# 6_BATT_5V.net
KiCad netlist of a schematic drawn in Altium Designer
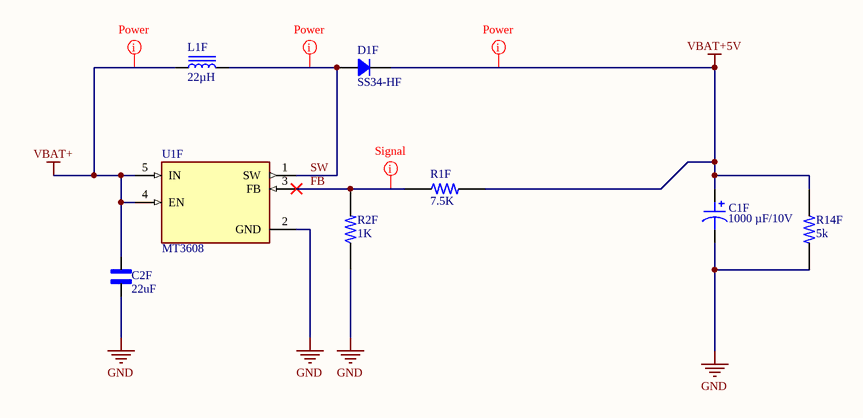
[diagram p0: 6_BATT+5V.SchDoc]

(export (version "E")
  (design (tool "Eeschema 10.0.6"))
  (components
    (comp (ref "C1F")
      (value "1000 µF/10V")
      (footprint "CAP AL TH D8 L3.5 H12.5")
      (description "CAP ALUM 1000UF 20% 6.3V RADIAL")
      (fields
        (field (name "PART NUMBER") "ECA-0JHG102")
        (field (name "MANUFACTURER") "Panasonic Electronic Components")
      )
      (libsource (lib "ESP-12F_WLED_IOT_LIPO") (part "Polarised Capacitor"))
    )
    (comp (ref "C2F")
      (value "22uF")
      (footprint "C-0603")
      (description "Ceramic Capacitor 16V 0603 (1608 Metric)")
      (fields (field (name "MP") "C0603C104J4RAC") (field (name "MF") "KEMET"))
      (libsource (lib "ESP-12F_WLED_IOT_LIPO") (part "C-0603"))
    )
    (comp (ref "D1F")
      (value "SS34-HF")
      (footprint "DO214AC SMA")
      (description "DIODE SCHOTTKY 40V 3A DO214AC")
      (fields (field (name "MANUFACTURER") "Comchip Technology"))
      (libsource (lib "ESP-12F_WLED_IOT_LIPO") (part "Diode"))
    )
    (comp (ref "L1F")
      (value "22µH")
      (footprint "TDK SLF7032")
      (description "FIXED IND 22UH 960MA 132 MOHM")
      (fields
        (field (name "PART NUMBER") "SLF7032T-220MR96-2PF")
        (field (name "MANUFACTURER") "TDK Corporation")
      )
      (libsource (lib "ESP-12F_WLED_IOT_LIPO") (part "Inductor"))
    )
    (comp (ref "R1F")
      (value "7.5K")
      (footprint "R-0603")
      (description "0603")
      (fields (field (name "MP") "2-1623703-0") (field (name "TOLERANCE") "1%"))
      (libsource (lib "ESP-12F_WLED_IOT_LIPO") (part "R-0603"))
    )
    (comp (ref "R2F")
      (value "1K")
      (footprint "R-0603")
      (description "0603")
      (fields (field (name "MP") "2-1623703-0") (field (name "TOLERANCE") "1%"))
      (libsource (lib "ESP-12F_WLED_IOT_LIPO") (part "R-0603"))
    )
    (comp (ref "R14F")
      (value "5k")
      (footprint "R-0603")
      (description "0603")
      (fields (field (name "MP") "2-1623703-0") (field (name "TOLERANCE") "1%"))
      (libsource (lib "ESP-12F_WLED_IOT_LIPO") (part "R-0603"))
    )
    (comp (ref "U1F")
      (value "MT3608")
      (footprint "MT3608-SOT23")
      (description "High Efficiency 1.2MHz 2A Step Up Converter")
      (libsource (lib "ESP-12F_WLED_IOT_LIPO") (part "MT3608"))
    )
  )
  (nets
    (net (code "1") (name "/FB") (class "Default")
      (node (ref "R1F") (pin "1") (pinfunction "1_1") (pintype "passive"))
      (node (ref "R2F") (pin "2") (pinfunction "2_2") (pintype "passive"))
      (node (ref "U1F") (pin "3") (pinfunction "FB_3") (pintype "input"))
    )
    (net (code "2") (name "/SW") (class "Default")
      (node (ref "D1F") (pin "1") (pinfunction "1_1") (pintype "passive"))
      (node (ref "L1F") (pin "2") (pinfunction "2_2") (pintype "passive"))
      (node (ref "U1F") (pin "1") (pinfunction "SW_1") (pintype "output"))
    )
    (net (code "3") (name "GND") (class "Default")
      (node (ref "C1F") (pin "2") (pinfunction "2_2") (pintype "passive"))
      (node (ref "C2F") (pin "1") (pinfunction "1_1") (pintype "passive"))
      (node (ref "R14F") (pin "2") (pinfunction "2_2") (pintype "passive"))
      (node (ref "R2F") (pin "1") (pinfunction "1_1") (pintype "passive"))
      (node (ref "U1F") (pin "2") (pinfunction "GND_2") (pintype "power_in"))
    )
    (net (code "4") (name "VBAT+") (class "Default")
      (node (ref "C2F") (pin "2") (pinfunction "2_2") (pintype "passive"))
      (node (ref "L1F") (pin "1") (pinfunction "1_1") (pintype "passive"))
      (node (ref "U1F") (pin "4") (pinfunction "EN_4") (pintype "input"))
      (node (ref "U1F") (pin "5") (pinfunction "IN_5") (pintype "input"))
    )
    (net (code "5") (name "VBAT+5V") (class "Default")
      (node (ref "C1F") (pin "1") (pinfunction "1_1") (pintype "passive"))
      (node (ref "D1F") (pin "2") (pinfunction "2_2") (pintype "passive"))
      (node (ref "R14F") (pin "1") (pinfunction "1_1") (pintype "passive"))
      (node (ref "R1F") (pin "2") (pinfunction "2_2") (pintype "passive"))
    )
  )
)
